# LightDiming2.net
KiCad netlist of a schematic drawn in EAGLE
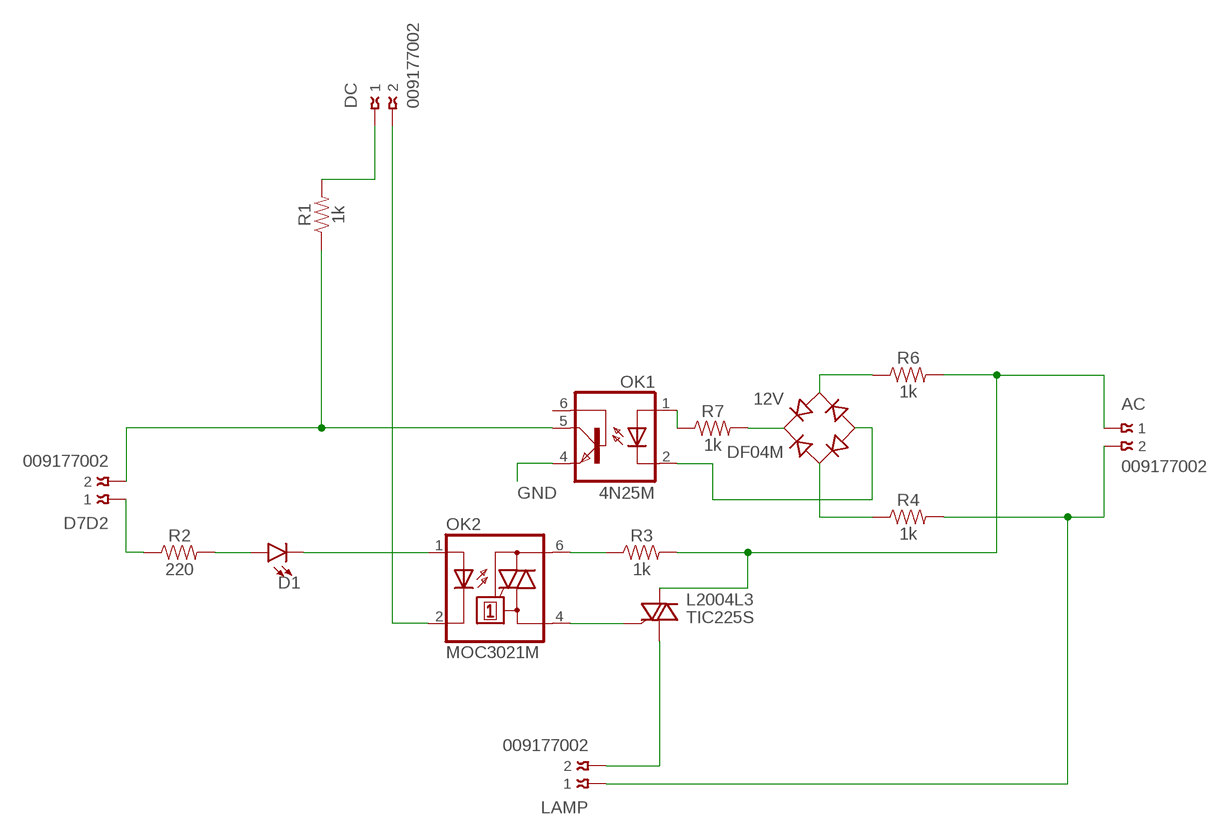
[diagram p0: schematic, sheet 1]

(export (version "E")
  (design (tool "Eeschema 10.0.6"))
  (components
    (comp (ref "AC")
      (value "009177002")
      (footprint "eagle-import:009177002")
      (fields (field (name "MPN") "009177002001006"))
      (libsource (lib "eagle-import") (part "00917?0027"))
    )
    (comp (ref "D1")
      (value "LED1206")
      (footprint "eagle-import:LED-1206")
      (libsource (lib "eagle-import") (part "LED1206"))
    )
    (comp (ref "D7D2")
      (value "009177002")
      (footprint "eagle-import:009177002")
      (fields (field (name "MPN") "009177002001006"))
      (libsource (lib "eagle-import") (part "00917?0027"))
    )
    (comp (ref "DC")
      (value "009177002")
      (footprint "eagle-import:009177002")
      (fields (field (name "MPN") "009177002001006"))
      (libsource (lib "eagle-import") (part "00917?0027"))
    )
    (comp (ref "DF04M")
      (value "12V")
      (footprint "eagle-import:B-DIL")
      (libsource (lib "eagle-import") (part "B-DIL"))
    )
    (comp (ref "L2004L3")
      (value "TIC225S")
      (footprint "eagle-import:TO220DS")
      (libsource (lib "eagle-import") (part "TIC225S"))
    )
    (comp (ref "LAMP")
      (value "009177002")
      (footprint "eagle-import:009177002")
      (fields (field (name "MPN") "009177002001006"))
      (libsource (lib "eagle-import") (part "00917?0027"))
    )
    (comp (ref "OK1")
      (value "4N25M")
      (footprint "eagle-import:DIL06")
      (fields (field (name "MPN") "4N25-M"))
      (libsource (lib "eagle-import") (part "4N?M25"))
    )
    (comp (ref "OK2")
      (value "MOC3021M")
      (footprint "eagle-import:DIL06")
      (fields (field (name "MF") "FAIRCHILD SEMICONDUCTOR") (field (name "MPN") "MOC3021-M"))
      (libsource (lib "eagle-import") (part "MOC30M21"))
    )
    (comp (ref "R1")
      (value "1k")
      (footprint "eagle-import:AXIAL-0.3")
      (libsource (lib "eagle-import") (part "1KOHM-HORIZ-1/4W-1%"))
    )
    (comp (ref "R2")
      (value "220")
      (footprint "eagle-import:0805")
      (libsource (lib "eagle-import") (part "0.75OHM-0805-1/4W-1%"))
    )
    (comp (ref "R3")
      (value "1k")
      (footprint "eagle-import:AXIAL-0.3")
      (libsource (lib "eagle-import") (part "1KOHM-HORIZ-1/4W-1%"))
    )
    (comp (ref "R4")
      (value "1k")
      (footprint "eagle-import:AXIAL-0.3")
      (libsource (lib "eagle-import") (part "1KOHM-HORIZ-1/4W-1%"))
    )
    (comp (ref "R6")
      (value "1k")
      (footprint "eagle-import:AXIAL-0.3")
      (libsource (lib "eagle-import") (part "1KOHM-HORIZ-1/4W-1%"))
    )
    (comp (ref "R7")
      (value "1k")
      (footprint "eagle-import:0805")
      (libsource (lib "eagle-import") (part "0.75OHM-0805-1/4W-1%"))
    )
  )
  (nets
    (net (code "1") (name "GND") (class "Default")
      (node (ref "AC") (pin "2") (pinfunction "2_2") (pintype "passive"))
      (node (ref "LAMP") (pin "1") (pinfunction "1_1") (pintype "passive"))
      (node (ref "OK1") (pin "4") (pinfunction "EMI_4") (pintype "passive"))
      (node (ref "R4") (pin "P$2") (pinfunction "2_P$2") (pintype "passive"))
    )
    (net (code "2") (name "Net-(D1-PadA)") (class "Default")
      (node (ref "D1") (pin "A") (pinfunction "A_A") (pintype "passive"))
      (node (ref "R2") (pin "2") (pinfunction "2_2") (pintype "passive"))
    )
    (net (code "3") (name "Net-(D7D2-Pad1)") (class "Default")
      (node (ref "D7D2") (pin "1") (pinfunction "1_1") (pintype "passive"))
      (node (ref "R2") (pin "1") (pinfunction "1_1") (pintype "passive"))
    )
    (net (code "4") (name "Net-(DF04M-Pad+)") (class "Default")
      (node (ref "DF04M") (pin "+") (pinfunction "+_+") (pintype "passive"))
      (node (ref "R7") (pin "2") (pinfunction "2_2") (pintype "passive"))
    )
    (net (code "5") (name "Net-(L2004L3-PadA1)") (class "Default")
      (node (ref "L2004L3") (pin "A1") (pinfunction "A1_A1") (pintype "passive"))
      (node (ref "LAMP") (pin "2") (pinfunction "2_2") (pintype "passive"))
    )
    (net (code "6") (name "Net-(OK1-A)") (class "Default")
      (node (ref "OK1") (pin "1") (pinfunction "A_1") (pintype "passive"))
      (node (ref "R7") (pin "1") (pinfunction "1_1") (pintype "passive"))
    )
    (net (code "7") (name "Net-(OK1-C)") (class "Default")
      (node (ref "DF04M") (pin "-") (pinfunction "-_-") (pintype "passive"))
      (node (ref "OK1") (pin "2") (pinfunction "C_2") (pintype "passive"))
    )
    (net (code "8") (name "Net-(OK1-COL)") (class "Default")
      (node (ref "D7D2") (pin "2") (pinfunction "2_2") (pintype "passive"))
      (node (ref "OK1") (pin "5") (pinfunction "COL_5") (pintype "passive"))
      (node (ref "R1") (pin "P$1") (pinfunction "1_P$1") (pintype "passive"))
    )
    (net (code "9") (name "Net-(OK2-A)") (class "Default")
      (node (ref "D1") (pin "C") (pinfunction "C_C") (pintype "passive"))
      (node (ref "OK2") (pin "1") (pinfunction "A_1") (pintype "passive"))
    )
    (net (code "10") (name "Net-(OK2-A1)") (class "Default")
      (node (ref "L2004L3") (pin "G") (pinfunction "G_G") (pintype "passive"))
      (node (ref "OK2") (pin "4") (pinfunction "A1_4") (pintype "passive"))
    )
    (net (code "11") (name "Net-(OK2-A2)") (class "Default")
      (node (ref "OK2") (pin "6") (pinfunction "A2_6") (pintype "passive"))
      (node (ref "R3") (pin "P$1") (pinfunction "1_P$1") (pintype "passive"))
    )
    (net (code "12") (name "Net-(OK2-C)") (class "Default")
      (node (ref "DC") (pin "2") (pinfunction "2_2") (pintype "passive"))
      (node (ref "OK2") (pin "2") (pinfunction "C_2") (pintype "passive"))
    )
    (net (code "13") (name "Net-(R1-2)") (class "Default")
      (node (ref "DC") (pin "1") (pinfunction "1_1") (pintype "passive"))
      (node (ref "R1") (pin "P$2") (pinfunction "2_P$2") (pintype "passive"))
    )
    (net (code "14") (name "Net-(R3-2)") (class "Default")
      (node (ref "AC") (pin "1") (pinfunction "1_1") (pintype "passive"))
      (node (ref "L2004L3") (pin "A2") (pinfunction "A2_A2") (pintype "passive"))
      (node (ref "R3") (pin "P$2") (pinfunction "2_P$2") (pintype "passive"))
      (node (ref "R6") (pin "P$2") (pinfunction "2_P$2") (pintype "passive"))
    )
    (net (code "15") (name "Net-(R4-1)") (class "Default")
      (node (ref "DF04M") (pin "AC1") (pinfunction "AC1_AC1") (pintype "passive"))
      (node (ref "R4") (pin "P$1") (pinfunction "1_P$1") (pintype "passive"))
    )
    (net (code "16") (name "Net-(R6-1)") (class "Default")
      (node (ref "DF04M") (pin "AC2") (pinfunction "AC2_AC2") (pintype "passive"))
      (node (ref "R6") (pin "P$1") (pinfunction "1_P$1") (pintype "passive"))
    )
    (net (code "17") (name "unconnected-(OK1-BAS-Pad6)") (class "Default")
      (node (ref "OK1") (pin "6") (pinfunction "BAS_6") (pintype "passive"))
    )
  )
)
